# sch.net
KiCad netlist of a schematic drawn in EasyEDA
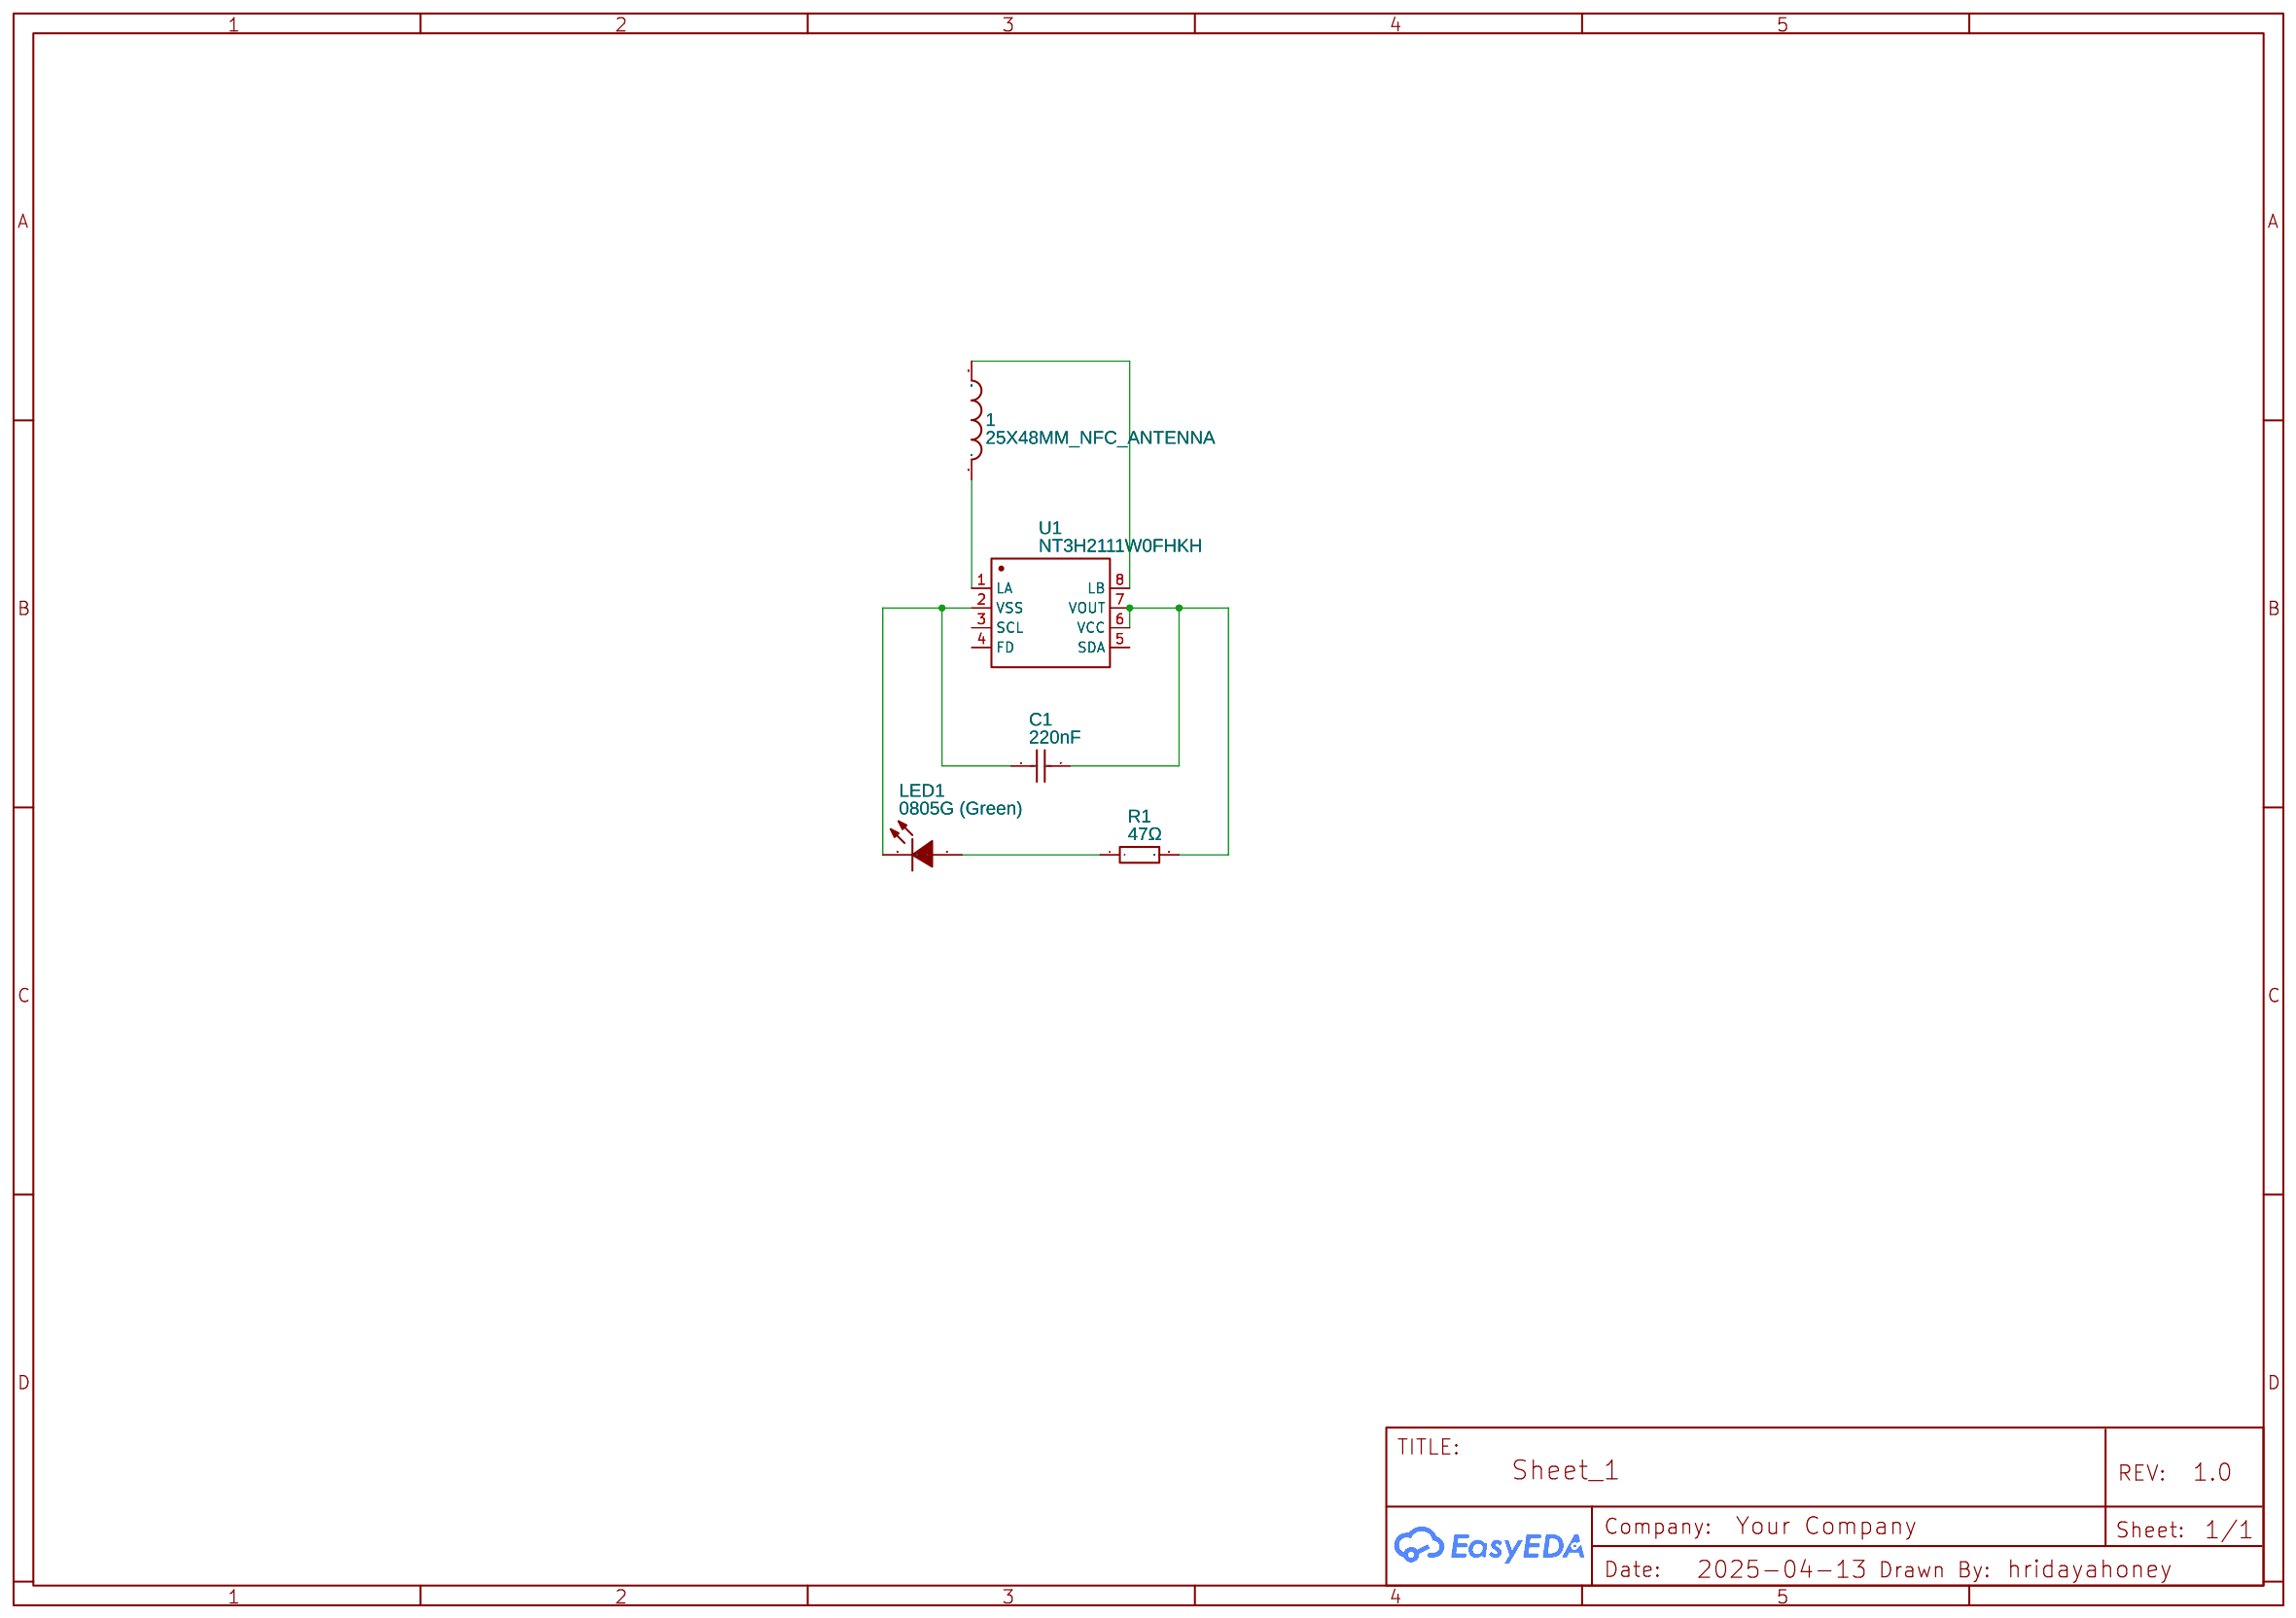
[diagram p0: schematic sheet]

(export (version "E")
  (design (tool "Eeschema 10.0.6"))
  (components
    (comp (ref "1") (value "25X48MM_NFC_ANTENNA") (libsource (lib "") (part "25X48MM_NFC_ANTENNA")))
    (comp (ref "C1")
      (value "220nF")
      (fields
        (field (name "Manufacturer Part") "CL10B224KA8NNNC")
        (field (name "Manufacturer") "SAMSUNG(三星)")
      )
      (libsource (lib "") (part "CL10B224KA8NNNC"))
    )
    (comp (ref "LED1")
      (value "0805G (Green)")
      (fields (field (name "Manufacturer Part") "KT-0805G") (field (name "Manufacturer") "KENTO"))
      (libsource (lib "") (part "0805G (Green)"))
    )
    (comp (ref "R1")
      (value "47Ω")
      (fields
        (field (name "Manufacturer Part") "0603WAF470JT5E")
        (field (name "Manufacturer") "UNI-ROYAL(厚声)")
      )
      (libsource (lib "") (part "0603WAF470JT5E"))
    )
    (comp (ref "U1")
      (value "NT3H2111W0FHKH")
      (fields (field (name "Manufacturer") "NXP(恩智浦)"))
      (libsource (lib "") (part "NT3H2111W0FHKH"))
    )
  )
  (nets
    (net (code "1") (name "Net-(LED1-A)") (class "Default")
      (node (ref "LED1") (pin "1") (pinfunction "A_1") (pintype "unspecified"))
      (node (ref "R1") (pin "1") (pinfunction "1_1") (pintype "input"))
    )
    (net (code "2") (name "Net-(LED1-K)") (class "Default")
      (node (ref "C1") (pin "1") (pinfunction "1_1") (pintype "input"))
      (node (ref "LED1") (pin "2") (pinfunction "K_2") (pintype "unspecified"))
      (node (ref "U1") (pin "2") (pinfunction "VSS_2") (pintype "unspecified"))
    )
    (net (code "3") (name "Net-(U1-LA)") (class "Default")
      (node (ref "1") (pin "P$2") (pinfunction "P$2_P$2") (pintype "bidirectional"))
      (node (ref "U1") (pin "1") (pinfunction "LA_1") (pintype "unspecified"))
    )
    (net (code "4") (name "Net-(U1-LB)") (class "Default")
      (node (ref "1") (pin "P$1") (pinfunction "P$1_P$1") (pintype "bidirectional"))
      (node (ref "U1") (pin "8") (pinfunction "LB_8") (pintype "unspecified"))
    )
    (net (code "5") (name "Net-(U1-VCC)") (class "Default")
      (node (ref "C1") (pin "2") (pinfunction "2_2") (pintype "input"))
      (node (ref "R1") (pin "2") (pinfunction "2_2") (pintype "input"))
      (node (ref "U1") (pin "6") (pinfunction "VCC_6") (pintype "unspecified"))
      (node (ref "U1") (pin "7") (pinfunction "VOUT_7") (pintype "unspecified"))
    )
    (net (code "6") (name "unconnected-(U1-FD-Pad4)") (class "Default")
      (node (ref "U1") (pin "4") (pinfunction "FD_4") (pintype "unspecified"))
    )
    (net (code "7") (name "unconnected-(U1-SCL-Pad3)") (class "Default")
      (node (ref "U1") (pin "3") (pinfunction "SCL_3") (pintype "unspecified"))
    )
    (net (code "8") (name "unconnected-(U1-SDA-Pad5)") (class "Default")
      (node (ref "U1") (pin "5") (pinfunction "SDA_5") (pintype "unspecified"))
    )
  )
)
